# DM3370_PCIe.net
KiCad netlist of a schematic drawn in Altium Designer
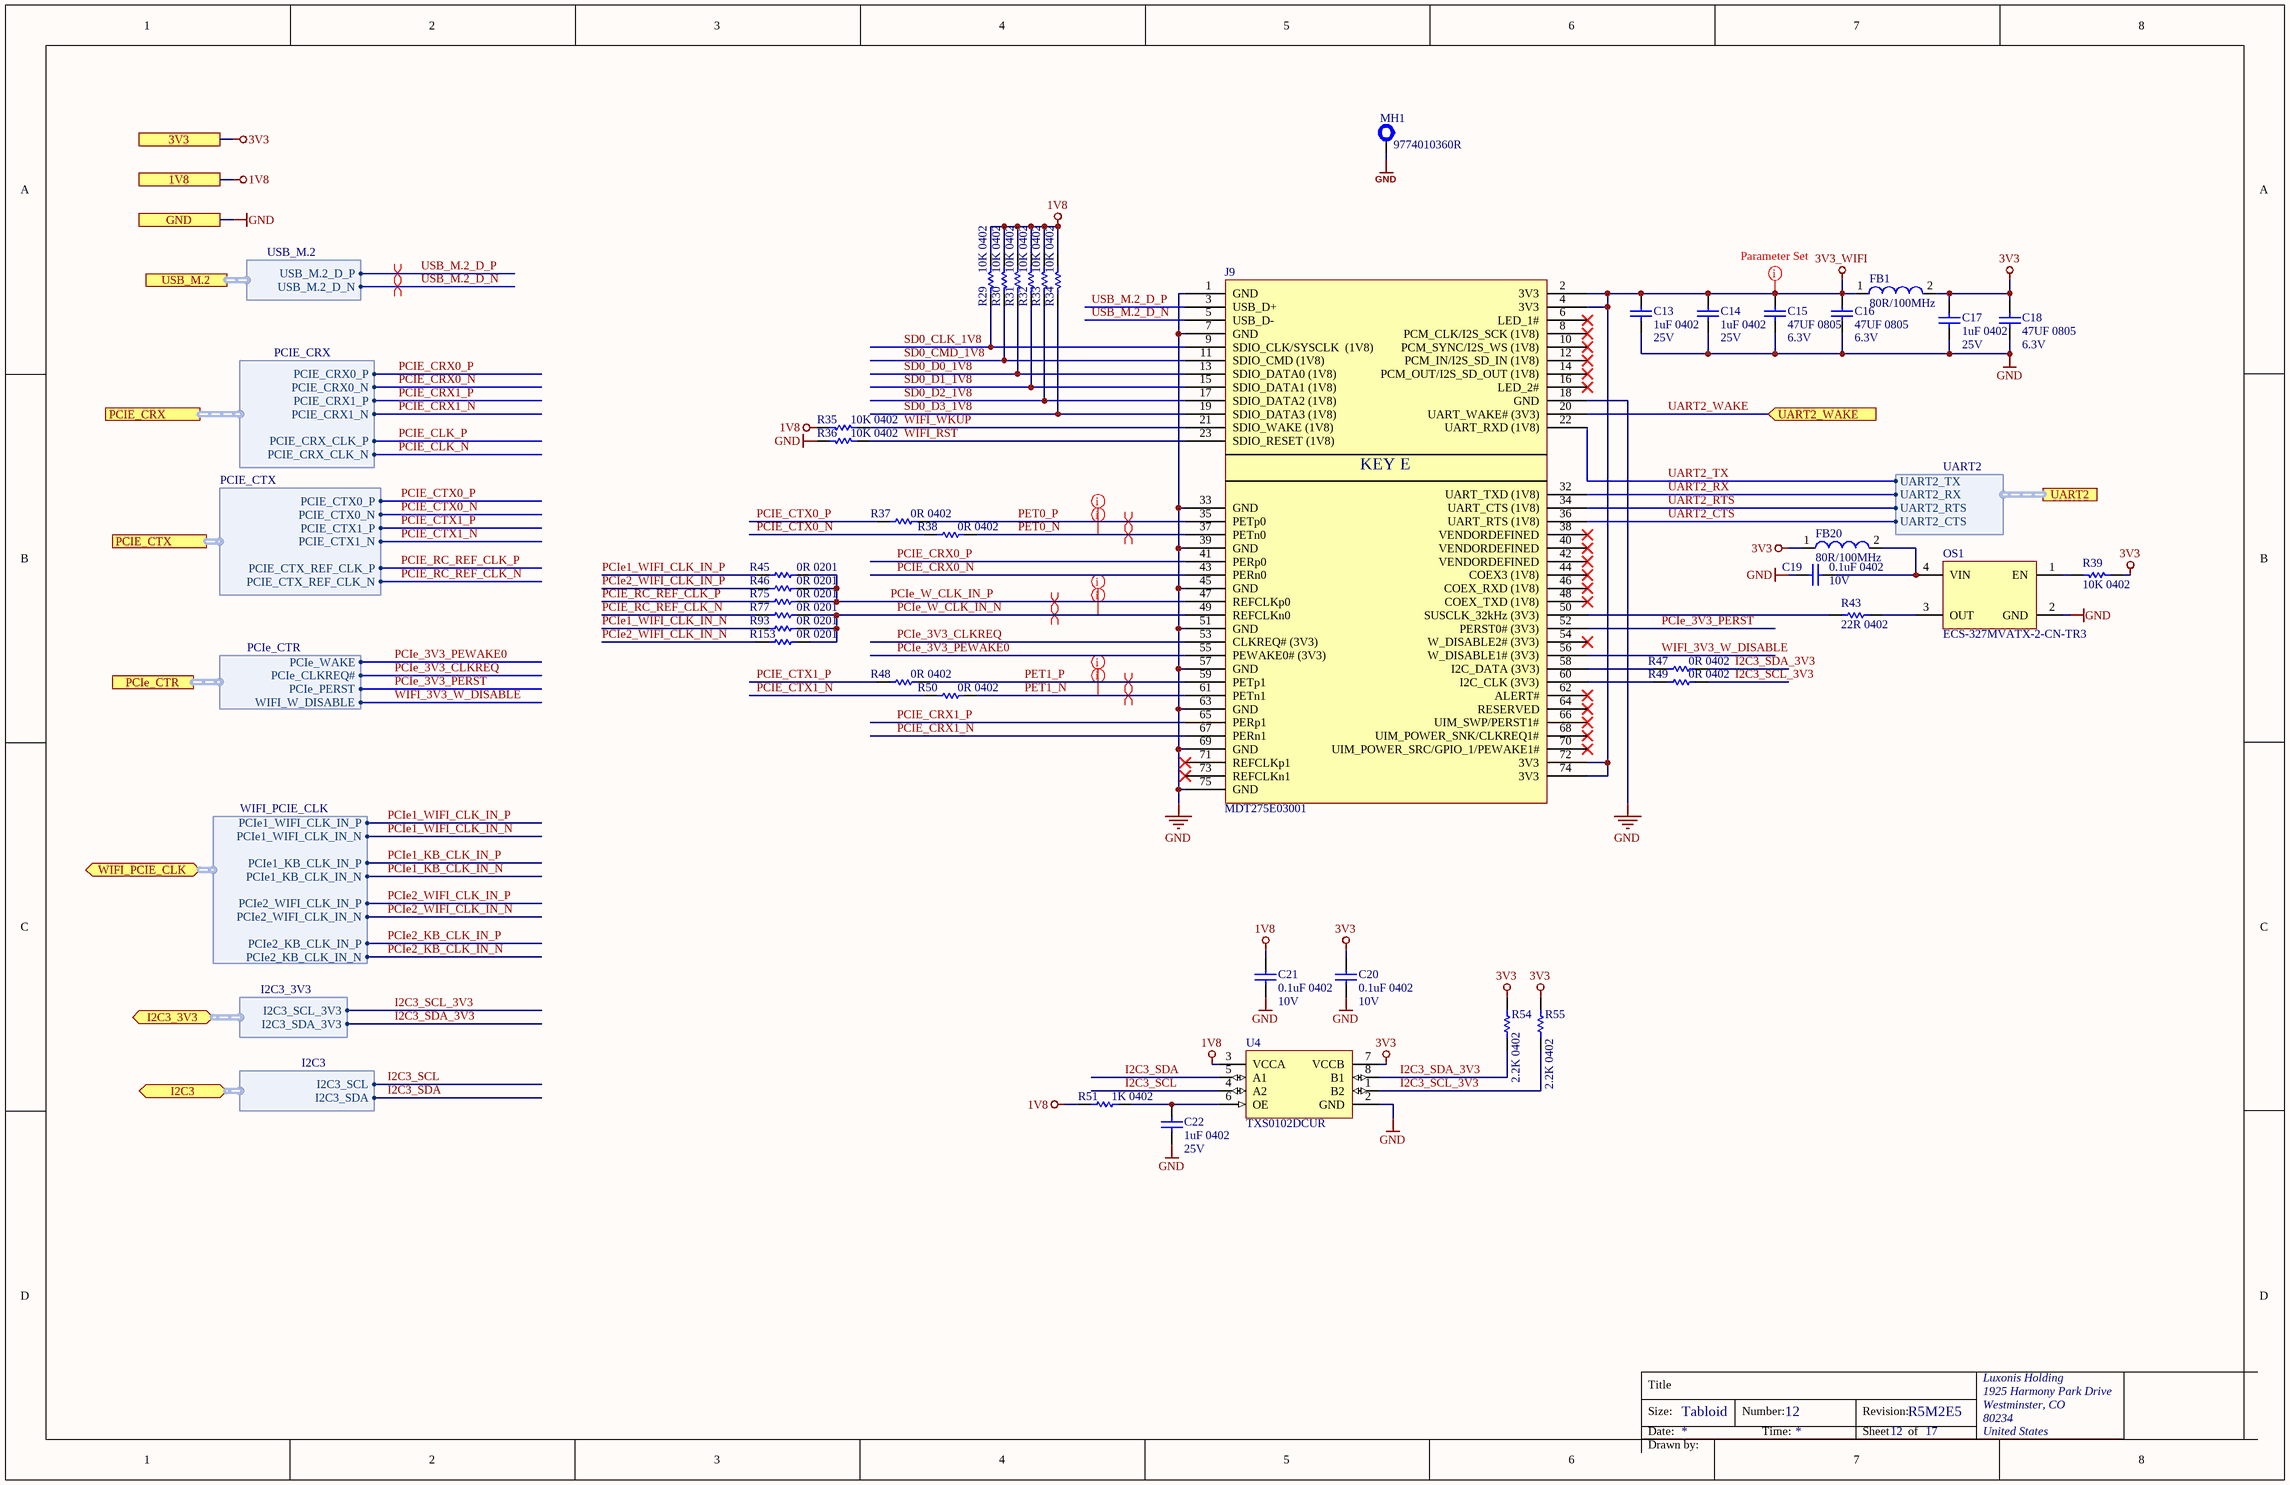
[diagram p0: DM3370_PCIe.SchDoc]

(export (version "E")
  (design (tool "Eeschema 10.0.6"))
  (components
    (comp (ref "C13")
      (value "1uF 0402")
      (footprint "CAP_Altium_Vault_Generic:CAPC0402(1005)70_L")
      (description "CAP CER 1UF 25V X5R 0402 10%")
      (fields
        (field (name "TOLERANCE") "10%")
        (field (name "VOLTAGE") "25V")
        (field (name "VOLTAGE RATING") "25V")
      )
      (libsource (lib "LuxonisMaster") (part "GRM155R61E105KA12D"))
    )
    (comp (ref "C14")
      (value "1uF 0402")
      (footprint "CAP_Altium_Vault_Generic:CAPC0402(1005)70_L")
      (description "CAP CER 1UF 25V X5R 0402 10%")
      (fields
        (field (name "TOLERANCE") "10%")
        (field (name "VOLTAGE") "25V")
        (field (name "VOLTAGE RATING") "25V")
      )
      (libsource (lib "LuxonisMaster") (part "GRM155R61E105KA12D"))
    )
    (comp (ref "C15")
      (value "47UF 0805")
      (footprint "CAP_Altium_Vault_Generic:CAPC0805(2012)145_L")
      (description "CAP CER 47UF 6.3V X5R 0805")
      (fields (field (name "TOLERANCE") "20%") (field (name "VOLTAGE") "6.3V"))
      (libsource (lib "LuxonisMaster") (part "GRM21BR60J476ME15L"))
    )
    (comp (ref "C16")
      (value "47UF 0805")
      (footprint "CAP_Altium_Vault_Generic:CAPC0805(2012)145_L")
      (description "CAP CER 47UF 6.3V X5R 0805")
      (fields (field (name "TOLERANCE") "20%") (field (name "VOLTAGE") "6.3V"))
      (libsource (lib "LuxonisMaster") (part "GRM21BR60J476ME15L"))
    )
    (comp (ref "C17")
      (value "1uF 0402")
      (footprint "CAP_Altium_Vault_Generic:CAPC0402(1005)70_L")
      (description "CAP CER 1UF 25V X5R 0402 10%")
      (fields
        (field (name "TOLERANCE") "10%")
        (field (name "VOLTAGE") "25V")
        (field (name "VOLTAGE RATING") "25V")
      )
      (libsource (lib "LuxonisMaster") (part "GRM155R61E105KA12D"))
    )
    (comp (ref "C18")
      (value "47UF 0805")
      (footprint "CAP_Altium_Vault_Generic:CAPC0805(2012)145_L")
      (description "CAP CER 47UF 6.3V X5R 0805")
      (fields (field (name "TOLERANCE") "20%") (field (name "VOLTAGE") "6.3V"))
      (libsource (lib "LuxonisMaster") (part "GRM21BR60J476ME15L"))
    )
    (comp (ref "C19")
      (value "0.1uF 0402")
      (footprint "CAP_Altium_Vault_Generic:CAPC0402(1005)70_L")
      (description "CAP CER 0.1UF 10V X7R 0402 5%")
      (fields (field (name "TOLERANCE") "5%") (field (name "VOLTAGE RATING") "10V"))
      (libsource (lib "LuxonisMaster") (part "GRM155R71A104JA01D"))
    )
    (comp (ref "C20")
      (value "0.1uF 0402")
      (footprint "CAP_Altium_Vault_Generic:CAPC0402(1005)70_L")
      (description "CAP CER 0.1UF 10V X7R 0402 5%")
      (fields (field (name "TOLERANCE") "5%") (field (name "VOLTAGE RATING") "10V"))
      (libsource (lib "LuxonisMaster") (part "GRM155R71A104JA01D"))
    )
    (comp (ref "C21")
      (value "0.1uF 0402")
      (footprint "CAP_Altium_Vault_Generic:CAPC0402(1005)70_L")
      (description "CAP CER 0.1UF 10V X7R 0402 5%")
      (fields (field (name "TOLERANCE") "5%") (field (name "VOLTAGE RATING") "10V"))
      (libsource (lib "LuxonisMaster") (part "GRM155R71A104JA01D"))
    )
    (comp (ref "C22")
      (value "1uF 0402")
      (footprint "CAP_Altium_Vault_Generic:CAPC0402(1005)70_L")
      (description "CAP CER 1UF 25V X5R 0402 10%")
      (fields
        (field (name "TOLERANCE") "10%")
        (field (name "VOLTAGE") "25V")
        (field (name "VOLTAGE RATING") "25V")
      )
      (libsource (lib "LuxonisMaster") (part "GRM155R61E105KA12D"))
    )
    (comp (ref "FB1")
      (value "80R/100MHz")
      (footprint "LuxonisMaster:BK1608HS800-T_L")
      (description "FERRITE BEAD 80 OHM 0603 1LN")
      (fields (field (name "TOLERANCE") "25%"))
      (libsource (lib "LuxonisMaster") (part "BK1608HS800-T"))
    )
    (comp (ref "FB20")
      (value "80R/100MHz")
      (footprint "LuxonisMaster:BK1608HS800-T_L")
      (description "FERRITE BEAD 80 OHM 0603 1LN")
      (fields (field (name "TOLERANCE") "25%"))
      (libsource (lib "LuxonisMaster") (part "BK1608HS800-T"))
    )
    (comp (ref "J9")
      (value "MDT275E03001")
      (footprint "MDT275E")
      (description "Conn Card Edge RCP 67 POS 0.5mm Solder RA SMD")
      (libsource (lib "Luxonis LLC") (part "MDT420E03001"))
    )
    (comp (ref "MH1")
      (value "9774010360R")
      (footprint "9774010360R")
      (description "Spacers/Standoffs")
      (libsource (lib "Luxonis LLC") (part "9774030243R"))
    )
    (comp (ref "OS1")
      (value "ECS-327MVATX-2-CN-TR3")
      (footprint "2520_OSC(FJ2400002)")
      (description "SMD Crystal Oscillator 32.768KHz 1.6V to 3.6V 15pF 4-Pin Miniature CSMD T/R")
      (libsource (lib "Luxonis LLC") (part "ECS-327MVATX-2-CN-TR3"))
    )
    (comp (ref "R29")
      (value "10K 0402")
      (footprint "RES_Altium_Vault_Generic:RESC0402(1005)_L")
      (fields (field (name "TOLERANCE") "1%"))
      (libsource (lib "LuxonisMaster") (part "RC0402FR-1310KL"))
    )
    (comp (ref "R30")
      (value "10K 0402")
      (footprint "RES_Altium_Vault_Generic:RESC0402(1005)_L")
      (fields (field (name "TOLERANCE") "1%"))
      (libsource (lib "LuxonisMaster") (part "RC0402FR-1310KL"))
    )
    (comp (ref "R31")
      (value "10K 0402")
      (footprint "RES_Altium_Vault_Generic:RESC0402(1005)_L")
      (fields (field (name "TOLERANCE") "1%"))
      (libsource (lib "LuxonisMaster") (part "RC0402FR-1310KL"))
    )
    (comp (ref "R32")
      (value "10K 0402")
      (footprint "RES_Altium_Vault_Generic:RESC0402(1005)_L")
      (fields (field (name "TOLERANCE") "1%"))
      (libsource (lib "LuxonisMaster") (part "RC0402FR-1310KL"))
    )
    (comp (ref "R33")
      (value "10K 0402")
      (footprint "RES_Altium_Vault_Generic:RESC0402(1005)_L")
      (fields (field (name "TOLERANCE") "1%"))
      (libsource (lib "LuxonisMaster") (part "RC0402FR-1310KL"))
    )
    (comp (ref "R34")
      (value "10K 0402")
      (footprint "RES_Altium_Vault_Generic:RESC0402(1005)_L")
      (fields (field (name "TOLERANCE") "1%"))
      (libsource (lib "LuxonisMaster") (part "RC0402FR-1310KL"))
    )
    (comp (ref "R35")
      (value "10K 0402")
      (footprint "RES_Altium_Vault_Generic:RESC0402(1005)_L")
      (fields (field (name "TOLERANCE") "1%"))
      (libsource (lib "LuxonisMaster") (part "RC0402FR-1310KL"))
    )
    (comp (ref "R36")
      (value "10K 0402")
      (footprint "RES_Altium_Vault_Generic:RESC0402(1005)_L")
      (fields (field (name "TOLERANCE") "1%"))
      (libsource (lib "LuxonisMaster") (part "RC0402FR-1310KL"))
    )
    (comp (ref "R37")
      (value "0R 0402")
      (footprint "RES_Altium_Vault_Generic:RESC0402(1005)_L")
      (description "RES SMD 0 OHM JUMPER 1/16W 0402")
      (fields (field (name "TOLERANCE") "5%"))
      (libsource (lib "LuxonisMaster") (part "CRCW04020000Z0ED"))
    )
    (comp (ref "R38")
      (value "0R 0402")
      (footprint "RES_Altium_Vault_Generic:RESC0402(1005)_L")
      (description "RES SMD 0 OHM JUMPER 1/16W 0402")
      (fields (field (name "TOLERANCE") "5%"))
      (libsource (lib "LuxonisMaster") (part "CRCW04020000Z0ED"))
    )
    (comp (ref "R39")
      (value "10K 0402")
      (footprint "RES_Altium_Vault_Generic:RESC0402(1005)_L")
      (fields (field (name "TOLERANCE") "1%"))
      (libsource (lib "LuxonisMaster") (part "RC0402FR-1310KL"))
    )
    (comp (ref "R43")
      (value "22R 0402")
      (footprint "RES_Altium_Vault_Generic:RESC0402(1005)_L")
      (description "RES SMD 22 OHM 1% 1/16W 0402")
      (fields (field (name "TOLERANCE") "1%"))
      (libsource (lib "BW2099_R0M0E0") (part "RC0402FR-0722RL"))
    )
    (comp (ref "R45")
      (value "0R 0201")
      (footprint "RESC0201(0603)_L")
      (description "RES SMD 0 OHM JUMPER 1/16W 0201")
      (libsource (lib "LuxonisMaster") (part "CRCW02010000Z0ED"))
    )
    (comp (ref "R46")
      (value "0R 0201")
      (footprint "RESC0201(0603)_L")
      (description "RES SMD 0 OHM JUMPER 1/16W 0201")
      (libsource (lib "LuxonisMaster") (part "CRCW02010000Z0ED"))
    )
    (comp (ref "R47")
      (value "0R 0402")
      (footprint "RES_Altium_Vault_Generic:RESC0402(1005)_L")
      (description "RES SMD 0 OHM JUMPER 1/16W 0402")
      (fields (field (name "TOLERANCE") "5%"))
      (libsource (lib "LuxonisMaster") (part "CRCW04020000Z0ED"))
    )
    (comp (ref "R48")
      (value "0R 0402")
      (footprint "RES_Altium_Vault_Generic:RESC0402(1005)_L")
      (description "RES SMD 0 OHM JUMPER 1/16W 0402")
      (fields (field (name "TOLERANCE") "5%"))
      (libsource (lib "LuxonisMaster") (part "CRCW04020000Z0ED"))
    )
    (comp (ref "R49")
      (value "0R 0402")
      (footprint "RES_Altium_Vault_Generic:RESC0402(1005)_L")
      (description "RES SMD 0 OHM JUMPER 1/16W 0402")
      (fields (field (name "TOLERANCE") "5%"))
      (libsource (lib "LuxonisMaster") (part "CRCW04020000Z0ED"))
    )
    (comp (ref "R50")
      (value "0R 0402")
      (footprint "RES_Altium_Vault_Generic:RESC0402(1005)_L")
      (description "RES SMD 0 OHM JUMPER 1/16W 0402")
      (fields (field (name "TOLERANCE") "5%"))
      (libsource (lib "LuxonisMaster") (part "CRCW04020000Z0ED"))
    )
    (comp (ref "R51")
      (value "1K 0402")
      (footprint "RES_Altium_Vault_Generic:RESC0402(1005)_L")
      (fields (field (name "TOLERANCE") "1%"))
      (libsource (lib "LuxonisMaster") (part "RC0402FR-071KL"))
    )
    (comp (ref "R54")
      (value "2.2K 0402")
      (footprint "RES_Altium_Vault_Generic:RESC0402(1005)_L")
      (description "RES SMD 2.2K OHM 1% 1/16W 0402")
      (fields (field (name "TOLERANCE") "1%"))
      (libsource (lib "LuxonisMaster") (part "RC0402FR-072K2L"))
    )
    (comp (ref "R55")
      (value "2.2K 0402")
      (footprint "RES_Altium_Vault_Generic:RESC0402(1005)_L")
      (description "RES SMD 2.2K OHM 1% 1/16W 0402")
      (fields (field (name "TOLERANCE") "1%"))
      (libsource (lib "LuxonisMaster") (part "RC0402FR-072K2L"))
    )
    (comp (ref "R75")
      (value "0R 0201")
      (footprint "RESC0201(0603)_L")
      (description "RES SMD 0 OHM JUMPER 1/16W 0201")
      (libsource (lib "LuxonisMaster") (part "CRCW02010000Z0ED"))
    )
    (comp (ref "R77")
      (value "0R 0201")
      (footprint "RESC0201(0603)_L")
      (description "RES SMD 0 OHM JUMPER 1/16W 0201")
      (libsource (lib "LuxonisMaster") (part "CRCW02010000Z0ED"))
    )
    (comp (ref "R93")
      (value "0R 0201")
      (footprint "RESC0201(0603)_L")
      (description "RES SMD 0 OHM JUMPER 1/16W 0201")
      (libsource (lib "LuxonisMaster") (part "CRCW02010000Z0ED"))
    )
    (comp (ref "R153")
      (value "0R 0201")
      (footprint "RESC0201(0603)_L")
      (description "RES SMD 0 OHM JUMPER 1/16W 0201")
      (libsource (lib "LuxonisMaster") (part "CRCW02010000Z0ED"))
    )
    (comp (ref "U4")
      (value "TXS0102DCUR")
      (footprint "TXS0102DCUR")
      (description "TEXAS INSTRUMENTS - TXS0102DCUR - IC, TRANSLATOR, 2 BIT, BI, US-8")
      (libsource (lib "Luxonis LLC") (part "TXS0102DCUR"))
    )
  )
  (nets
    (net (code "9") (name "/I2C3_SCL") (class "Default")
      (node (ref "U4") (pin "4") (pinfunction "A2_4") (pintype "bidirectional"))
    )
    (net (code "10") (name "/I2C3_SCL_3V3") (class "Default")
      (node (ref "R49") (pin "2") (pinfunction "2_2") (pintype "passive"))
      (node (ref "R55") (pin "1") (pinfunction "1_1") (pintype "passive"))
      (node (ref "U4") (pin "1") (pinfunction "B2_1") (pintype "bidirectional"))
    )
    (net (code "11") (name "/I2C3_SDA") (class "Default")
      (node (ref "U4") (pin "5") (pinfunction "A1_5") (pintype "bidirectional"))
    )
    (net (code "12") (name "/I2C3_SDA_3V3") (class "Default")
      (node (ref "R47") (pin "2") (pinfunction "2_2") (pintype "passive"))
      (node (ref "R54") (pin "1") (pinfunction "1_1") (pintype "passive"))
      (node (ref "U4") (pin "8") (pinfunction "B1_8") (pintype "bidirectional"))
    )
    (net (code "15") (name "/PCIE_CRX0_N") (class "Default")
      (node (ref "J9") (pin "43") (pinfunction "PERn0_43") (pintype "passive"))
    )
    (net (code "16") (name "/PCIE_CRX0_P") (class "Default")
      (node (ref "J9") (pin "41") (pinfunction "PERp0_41") (pintype "passive"))
    )
    (net (code "17") (name "/PCIE_CRX1_N") (class "Default")
      (node (ref "J9") (pin "67") (pinfunction "PERn1_67") (pintype "passive"))
    )
    (net (code "18") (name "/PCIE_CRX1_P") (class "Default")
      (node (ref "J9") (pin "65") (pinfunction "PERp1_65") (pintype "passive"))
    )
    (net (code "19") (name "/PCIE_CTX0_N") (class "Default")
      (node (ref "R38") (pin "1") (pinfunction "1_1") (pintype "passive"))
    )
    (net (code "20") (name "/PCIE_CTX0_P") (class "Default")
      (node (ref "R37") (pin "1") (pinfunction "1_1") (pintype "passive"))
    )
    (net (code "21") (name "/PCIE_CTX1_N") (class "Default")
      (node (ref "R50") (pin "1") (pinfunction "1_1") (pintype "passive"))
    )
    (net (code "22") (name "/PCIE_CTX1_P") (class "Default")
      (node (ref "R48") (pin "1") (pinfunction "1_1") (pintype "passive"))
    )
    (net (code "23") (name "/PCIE_RC_REF_CLK_N") (class "Default")
      (node (ref "R77") (pin "1") (pinfunction "1_1") (pintype "passive"))
    )
    (net (code "24") (name "/PCIE_RC_REF_CLK_P") (class "Default")
      (node (ref "R75") (pin "1") (pinfunction "1_1") (pintype "passive"))
    )
    (net (code "27") (name "/PCIe1_WIFI_CLK_IN_N") (class "Default")
      (node (ref "R93") (pin "1") (pinfunction "1_1") (pintype "passive"))
    )
    (net (code "28") (name "/PCIe1_WIFI_CLK_IN_P") (class "Default")
      (node (ref "R45") (pin "1") (pinfunction "1_1") (pintype "passive"))
    )
    (net (code "31") (name "/PCIe2_WIFI_CLK_IN_N") (class "Default")
      (node (ref "R153") (pin "1") (pinfunction "1_1") (pintype "passive"))
    )
    (net (code "32") (name "/PCIe2_WIFI_CLK_IN_P") (class "Default")
      (node (ref "R46") (pin "1") (pinfunction "1_1") (pintype "passive"))
    )
    (net (code "33") (name "/PCIe_3V3_CLKREQ") (class "Default")
      (node (ref "J9") (pin "53") (pinfunction "CLKREQ#_(3V3)_53") (pintype "passive"))
    )
    (net (code "34") (name "/PCIe_3V3_PERST") (class "Default")
      (node (ref "J9") (pin "52") (pinfunction "PERST0#_(3V3)_52") (pintype "passive"))
    )
    (net (code "35") (name "/PCIe_3V3_PEWAKE0") (class "Default")
      (node (ref "J9") (pin "55") (pinfunction "PEWAKE0#_(3V3)_55") (pintype "passive"))
    )
    (net (code "36") (name "/PCIe_W_CLK_IN_N") (class "Default")
      (node (ref "J9") (pin "49") (pinfunction "REFCLKn0_49") (pintype "passive"))
      (node (ref "R153") (pin "2") (pinfunction "2_2") (pintype "passive"))
      (node (ref "R77") (pin "2") (pinfunction "2_2") (pintype "passive"))
      (node (ref "R93") (pin "2") (pinfunction "2_2") (pintype "passive"))
    )
    (net (code "37") (name "/PCIe_W_CLK_IN_P") (class "Default")
      (node (ref "J9") (pin "47") (pinfunction "REFCLKp0_47") (pintype "passive"))
      (node (ref "R45") (pin "2") (pinfunction "2_2") (pintype "passive"))
      (node (ref "R46") (pin "2") (pinfunction "2_2") (pintype "passive"))
      (node (ref "R75") (pin "2") (pinfunction "2_2") (pintype "passive"))
    )
    (net (code "38") (name "/PET0_N") (class "Default")
      (node (ref "J9") (pin "37") (pinfunction "PETn0_37") (pintype "passive"))
      (node (ref "R38") (pin "2") (pinfunction "2_2") (pintype "passive"))
    )
    (net (code "39") (name "/PET0_P") (class "Default")
      (node (ref "J9") (pin "35") (pinfunction "PETp0_35") (pintype "passive"))
      (node (ref "R37") (pin "2") (pinfunction "2_2") (pintype "passive"))
    )
    (net (code "40") (name "/PET1_N") (class "Default")
      (node (ref "J9") (pin "61") (pinfunction "PETn1_61") (pintype "passive"))
      (node (ref "R50") (pin "2") (pinfunction "2_2") (pintype "passive"))
    )
    (net (code "41") (name "/PET1_P") (class "Default")
      (node (ref "J9") (pin "59") (pinfunction "PETp1_59") (pintype "passive"))
      (node (ref "R48") (pin "2") (pinfunction "2_2") (pintype "passive"))
    )
    (net (code "42") (name "/SD0_CLK_1V8") (class "Default")
      (node (ref "J9") (pin "9") (pinfunction "SDIO_CLK/SYSCLK__(1V8)_9") (pintype "passive"))
      (node (ref "R29") (pin "2") (pinfunction "2_2") (pintype "passive"))
    )
    (net (code "43") (name "/SD0_CMD_1V8") (class "Default")
      (node (ref "J9") (pin "11") (pinfunction "SDIO_CMD_(1V8)_11") (pintype "passive"))
      (node (ref "R30") (pin "2") (pinfunction "2_2") (pintype "passive"))
    )
    (net (code "44") (name "/SD0_D0_1V8") (class "Default")
      (node (ref "J9") (pin "13") (pinfunction "SDIO_DATA0_(1V8)_13") (pintype "passive"))
      (node (ref "R31") (pin "2") (pinfunction "2_2") (pintype "passive"))
    )
    (net (code "45") (name "/SD0_D1_1V8") (class "Default")
      (node (ref "J9") (pin "15") (pinfunction "SDIO_DATA1_(1V8)_15") (pintype "passive"))
      (node (ref "R32") (pin "2") (pinfunction "2_2") (pintype "passive"))
    )
    (net (code "46") (name "/SD0_D2_1V8") (class "Default")
      (node (ref "J9") (pin "17") (pinfunction "SDIO_DATA2_(1V8)_17") (pintype "passive"))
      (node (ref "R33") (pin "2") (pinfunction "2_2") (pintype "passive"))
    )
    (net (code "47") (name "/SD0_D3_1V8") (class "Default")
      (node (ref "J9") (pin "19") (pinfunction "SDIO_DATA3_(1V8)_19") (pintype "passive"))
      (node (ref "R34") (pin "2") (pinfunction "2_2") (pintype "passive"))
    )
    (net (code "48") (name "/UART2_CTS") (class "Default")
      (node (ref "J9") (pin "36") (pinfunction "UART_RTS_(1V8)_36") (pintype "passive"))
    )
    (net (code "49") (name "/UART2_RTS") (class "Default")
      (node (ref "J9") (pin "34") (pinfunction "UART_CTS_(1V8)_34") (pintype "passive"))
    )
    (net (code "50") (name "/UART2_RX") (class "Default")
      (node (ref "J9") (pin "32") (pinfunction "UART_TXD_(1V8)_32") (pintype "passive"))
    )
    (net (code "51") (name "/UART2_TX") (class "Default")
      (node (ref "J9") (pin "22") (pinfunction "UART_RXD_(1V8)_22") (pintype "passive"))
    )
    (net (code "52") (name "/UART2_WAKE") (class "Default")
      (node (ref "J9") (pin "20") (pinfunction "UART_WAKE#_(3V3)_20") (pintype "passive"))
    )
    (net (code "53") (name "/USB_M.2_D_N") (class "Default")
      (node (ref "J9") (pin "5") (pinfunction "USB_D-_5") (pintype "passive"))
    )
    (net (code "54") (name "/USB_M.2_D_P") (class "Default")
      (node (ref "J9") (pin "3") (pinfunction "USB_D+_3") (pintype "passive"))
    )
    (net (code "55") (name "/WIFI_3V3_W_DISABLE") (class "Default")
      (node (ref "J9") (pin "56") (pinfunction "W_DISABLE1#_(3V3)_56") (pintype "passive"))
    )
    (net (code "56") (name "/WIFI_RST") (class "Default")
      (node (ref "J9") (pin "23") (pinfunction "SDIO_RESET_(1V8)_23") (pintype "passive"))
      (node (ref "R36") (pin "1") (pinfunction "1_1") (pintype "passive"))
    )
    (net (code "57") (name "/WIFI_WKUP") (class "Default")
      (node (ref "J9") (pin "21") (pinfunction "SDIO_WAKE_(1V8)_21") (pintype "passive"))
      (node (ref "R35") (pin "1") (pinfunction "1_1") (pintype "passive"))
    )
    (net (code "66") (name "1V8") (class "Default")
      (node (ref "C21") (pin "2") (pinfunction "2_2") (pintype "passive"))
      (node (ref "R29") (pin "1") (pinfunction "1_1") (pintype "passive"))
      (node (ref "R30") (pin "1") (pinfunction "1_1") (pintype "passive"))
      (node (ref "R31") (pin "1") (pinfunction "1_1") (pintype "passive"))
      (node (ref "R32") (pin "1") (pinfunction "1_1") (pintype "passive"))
      (node (ref "R33") (pin "1") (pinfunction "1_1") (pintype "passive"))
      (node (ref "R34") (pin "1") (pinfunction "1_1") (pintype "passive"))
      (node (ref "R35") (pin "2") (pinfunction "2_2") (pintype "passive"))
      (node (ref "R51") (pin "2") (pinfunction "2_2") (pintype "passive"))
      (node (ref "U4") (pin "3") (pinfunction "VCCA_3") (pintype "power_in"))
    )
    (net (code "67") (name "3V3") (class "Default")
      (node (ref "C17") (pin "2") (pinfunction "2_2") (pintype "passive"))
      (node (ref "C18") (pin "2") (pinfunction "2_2") (pintype "passive"))
      (node (ref "C20") (pin "2") (pinfunction "2_2") (pintype "passive"))
      (node (ref "FB1") (pin "2") (pinfunction "2_2") (pintype "passive"))
      (node (ref "FB20") (pin "1") (pinfunction "1_1") (pintype "passive"))
      (node (ref "R39") (pin "2") (pinfunction "2_2") (pintype "passive"))
      (node (ref "R54") (pin "2") (pinfunction "2_2") (pintype "passive"))
      (node (ref "R55") (pin "2") (pinfunction "2_2") (pintype "passive"))
      (node (ref "U4") (pin "7") (pinfunction "VCCB_7") (pintype "power_in"))
    )
    (net (code "68") (name "3V3_WIFI") (class "Default")
      (node (ref "C13") (pin "2") (pinfunction "2_2") (pintype "passive"))
      (node (ref "C14") (pin "2") (pinfunction "2_2") (pintype "passive"))
      (node (ref "C15") (pin "2") (pinfunction "2_2") (pintype "passive"))
      (node (ref "C16") (pin "2") (pinfunction "2_2") (pintype "passive"))
      (node (ref "FB1") (pin "1") (pinfunction "1_1") (pintype "passive"))
      (node (ref "J9") (pin "2") (pinfunction "3V3_2") (pintype "passive"))
      (node (ref "J9") (pin "4") (pinfunction "3V3_4") (pintype "passive"))
      (node (ref "J9") (pin "72") (pinfunction "3V3_72") (pintype "passive"))
      (node (ref "J9") (pin "74") (pinfunction "3V3_74") (pintype "passive"))
    )
    (net (code "69") (name "GND") (class "Default")
      (node (ref "C13") (pin "1") (pinfunction "1_1") (pintype "passive"))
      (node (ref "C14") (pin "1") (pinfunction "1_1") (pintype "passive"))
      (node (ref "C15") (pin "1") (pinfunction "1_1") (pintype "passive"))
      (node (ref "C16") (pin "1") (pinfunction "1_1") (pintype "passive"))
      (node (ref "C17") (pin "1") (pinfunction "1_1") (pintype "passive"))
      (node (ref "C18") (pin "1") (pinfunction "1_1") (pintype "passive"))
      (node (ref "C19") (pin "1") (pinfunction "1_1") (pintype "passive"))
      (node (ref "C20") (pin "1") (pinfunction "1_1") (pintype "passive"))
      (node (ref "C21") (pin "1") (pinfunction "1_1") (pintype "passive"))
      (node (ref "C22") (pin "1") (pinfunction "1_1") (pintype "passive"))
      (node (ref "J9") (pin "1") (pinfunction "GND_1") (pintype "passive"))
      (node (ref "J9") (pin "18") (pinfunction "GND_18") (pintype "passive"))
      (node (ref "J9") (pin "33") (pinfunction "GND_33") (pintype "passive"))
      (node (ref "J9") (pin "39") (pinfunction "GND_39") (pintype "passive"))
      (node (ref "J9") (pin "45") (pinfunction "GND_45") (pintype "passive"))
      (node (ref "J9") (pin "51") (pinfunction "GND_51") (pintype "passive"))
      (node (ref "J9") (pin "57") (pinfunction "GND_57") (pintype "passive"))
      (node (ref "J9") (pin "63") (pinfunction "GND_63") (pintype "passive"))
      (node (ref "J9") (pin "69") (pinfunction "GND_69") (pintype "passive"))
      (node (ref "J9") (pin "7") (pinfunction "GND_7") (pintype "passive"))
      (node (ref "J9") (pin "75") (pinfunction "GND_75") (pintype "passive"))
      (node (ref "MH1") (pin "1") (pintype "passive"))
      (node (ref "OS1") (pin "2") (pinfunction "GND_2") (pintype "passive"))
      (node (ref "R36") (pin "2") (pinfunction "2_2") (pintype "passive"))
      (node (ref "U4") (pin "2") (pinfunction "GND_2") (pintype "power_in"))
    )
    (net (code "70") (name "Net-(J9-I2C_CLK_(3V3))") (class "Default")
      (node (ref "J9") (pin "60") (pinfunction "I2C_CLK_(3V3)_60") (pintype "passive"))
      (node (ref "R49") (pin "1") (pinfunction "1_1") (pintype "passive"))
    )
    (net (code "71") (name "Net-(J9-I2C_DATA_(3V3))") (class "Default")
      (node (ref "J9") (pin "58") (pinfunction "I2C_DATA_(3V3)_58") (pintype "passive"))
      (node (ref "R47") (pin "1") (pinfunction "1_1") (pintype "passive"))
    )
    (net (code "72") (name "Net-(J9-SUSCLK_32kHz_(3V3))") (class "Default")
      (node (ref "J9") (pin "50") (pinfunction "SUSCLK_32kHz_(3V3)_50") (pintype "passive"))
      (node (ref "R43") (pin "2") (pinfunction "2_2") (pintype "passive"))
    )
    (net (code "73") (name "Net-(OS1-EN)") (class "Default")
      (node (ref "OS1") (pin "1") (pinfunction "EN_1") (pintype "passive"))
      (node (ref "R39") (pin "1") (pinfunction "1_1") (pintype "passive"))
    )
    (net (code "74") (name "Net-(OS1-OUT)") (class "Default")
      (node (ref "OS1") (pin "3") (pinfunction "OUT_3") (pintype "passive"))
      (node (ref "R43") (pin "1") (pinfunction "1_1") (pintype "passive"))
    )
    (net (code "75") (name "Net-(OS1-VIN)") (class "Default")
      (node (ref "C19") (pin "2") (pinfunction "2_2") (pintype "passive"))
      (node (ref "FB20") (pin "2") (pinfunction "2_2") (pintype "passive"))
      (node (ref "OS1") (pin "4") (pinfunction "VIN_4") (pintype "passive"))
    )
    (net (code "76") (name "Net-(U4-OE)") (class "Default")
      (node (ref "C22") (pin "2") (pinfunction "2_2") (pintype "passive"))
      (node (ref "R51") (pin "1") (pinfunction "1_1") (pintype "passive"))
      (node (ref "U4") (pin "6") (pinfunction "OE_6") (pintype "input"))
    )
    (net (code "77") (name "unconnected-(J9-ALERT#-Pad62)") (class "Default")
      (node (ref "J9") (pin "62") (pinfunction "ALERT#_62") (pintype "passive+no_connect"))
    )
    (net (code "78") (name "unconnected-(J9-COEX3_(1V8)-Pad44)") (class "Default")
      (node (ref "J9") (pin "44") (pinfunction "COEX3_(1V8)_44") (pintype "passive+no_connect"))
    )
    (net (code "79") (name "unconnected-(J9-COEX_RXD_(1V8)-Pad46)") (class "Default")
      (node (ref "J9") (pin "46") (pinfunction "COEX_RXD_(1V8)_46") (pintype "passive+no_connect"))
    )
    (net (code "80") (name "unconnected-(J9-COEX_TXD_(1V8)-Pad48)") (class "Default")
      (node (ref "J9") (pin "48") (pinfunction "COEX_TXD_(1V8)_48") (pintype "passive+no_connect"))
    )
    (net (code "81") (name "unconnected-(J9-LED_1#-Pad6)") (class "Default")
      (node (ref "J9") (pin "6") (pinfunction "LED_1#_6") (pintype "passive+no_connect"))
    )
    (net (code "82") (name "unconnected-(J9-LED_2#-Pad16)") (class "Default")
      (node (ref "J9") (pin "16") (pinfunction "LED_2#_16") (pintype "passive+no_connect"))
    )
    (net (code "83") (name "unconnected-(J9-PCM_CLK{slash}I2S_SCK_(1V8)-Pad8)") (class "Default")
      (node (ref "J9") (pin "8") (pinfunction "PCM_CLK/I2S_SCK_(1V8)_8") (pintype "passive+no_connect"))
    )
    (net (code "84") (name "unconnected-(J9-PCM_IN{slash}I2S_SD_IN_(1V8)-Pad12)") (class "Default")
      (node (ref "J9") (pin "12") (pinfunction "PCM_IN/I2S_SD_IN_(1V8)_12") (pintype "passive+no_connect"))
    )
    (net (code "85") (name "unconnected-(J9-PCM_OUT{slash}I2S_SD_OUT_(1V8)-Pad14)") (class "Default")
      (node (ref "J9") (pin "14") (pinfunction "PCM_OUT/I2S_SD_OUT_(1V8)_14") (pintype "passive+no_connect"))
    )
    (net (code "86") (name "unconnected-(J9-PCM_SYNC{slash}I2S_WS_(1V8)-Pad10)") (class "Default")
      (node (ref "J9") (pin "10") (pinfunction "PCM_SYNC/I2S_WS_(1V8)_10") (pintype "passive+no_connect"))
    )
    (net (code "87") (name "unconnected-(J9-REFCLKn1-Pad73)") (class "Default")
      (node (ref "J9") (pin "73") (pinfunction "REFCLKn1_73") (pintype "passive+no_connect"))
    )
    (net (code "88") (name "unconnected-(J9-REFCLKp1-Pad71)") (class "Default")
      (node (ref "J9") (pin "71") (pinfunction "REFCLKp1_71") (pintype "passive+no_connect"))
    )
    (net (code "89") (name "unconnected-(J9-RESERVED-Pad64)") (class "Default")
      (node (ref "J9") (pin "64") (pinfunction "RESERVED_64") (pintype "passive+no_connect"))
    )
    (net (code "90") (name "unconnected-(J9-UIM_POWER_SNK{slash}CLKREQ1#-Pad68)") (class "Default")
      (node (ref "J9") (pin "68") (pinfunction "UIM_POWER_SNK/CLKREQ1#_68") (pintype "passive+no_connect"))
    )
    (net (code "91") (name "unconnected-(J9-UIM_POWER_SRC{slash}GPIO_1{slash}PEWAKE1#-Pad70)") (class "Default")
      (node (ref "J9") (pin "70") (pinfunction "UIM_POWER_SRC/GPIO_1/PEWAKE1#_70") (pintype "passive+no_connect"))
    )
    (net (code "92") (name "unconnected-(J9-UIM_SWP{slash}PERST1#-Pad66)") (class "Default")
      (node (ref "J9") (pin "66") (pinfunction "UIM_SWP/PERST1#_66") (pintype "passive+no_connect"))
    )
    (net (code "93") (name "unconnected-(J9-VENDORDEFINED-Pad38)") (class "Default")
      (node (ref "J9") (pin "38") (pinfunction "VENDORDEFINED_38") (pintype "passive+no_connect"))
    )
    (net (code "94") (name "unconnected-(J9-VENDORDEFINED-Pad40)") (class "Default")
      (node (ref "J9") (pin "40") (pinfunction "VENDORDEFINED_40") (pintype "passive+no_connect"))
    )
    (net (code "95") (name "unconnected-(J9-VENDORDEFINED-Pad42)") (class "Default")
      (node (ref "J9") (pin "42") (pinfunction "VENDORDEFINED_42") (pintype "passive+no_connect"))
    )
    (net (code "96") (name "unconnected-(J9-W_DISABLE2#_(3V3)-Pad54)") (class "Default")
      (node (ref "J9") (pin "54") (pinfunction "W_DISABLE2#_(3V3)_54") (pintype "passive+no_connect"))
    )
  )
)
